# digit_7.net
KiCad netlist of a schematic drawn in EAGLE
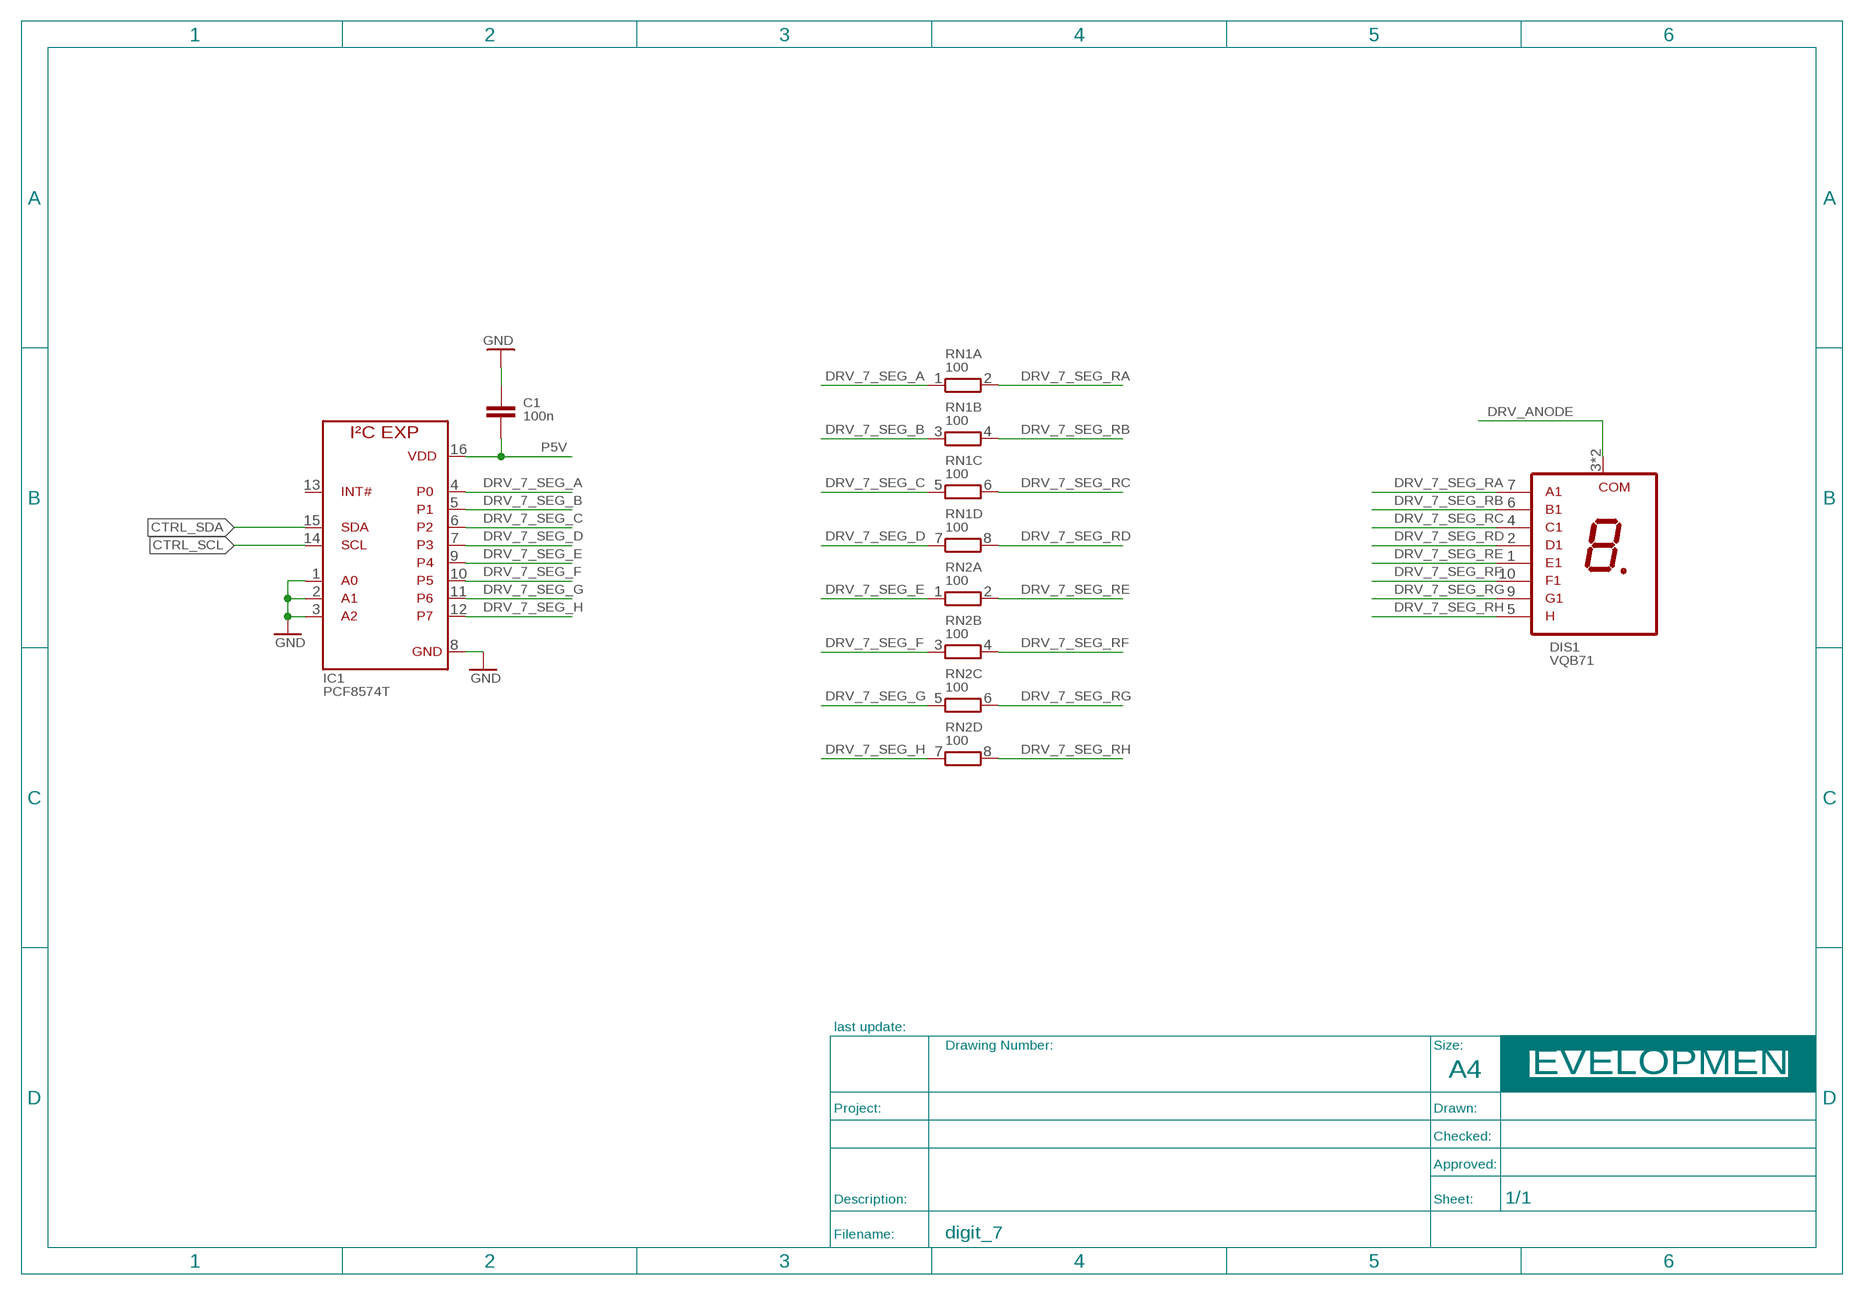
[diagram p0: schematic, sheet 1]

(export (version "E")
  (design (tool "Eeschema 10.0.6"))
  (components
    (comp (ref "C1")
      (value "100n")
      (footprint "eagle-import:S_0805")
      (fields (field (name "PART_CODE_BEL") "C_PAC_S_0805_VAL_100n"))
      (libsource (lib "eagle-import") (part "C_EU_S_0805"))
    )
    (comp (ref "DIS1")
      (value "VQB71")
      (footprint "eagle-import:T_VQB71")
      (libsource (lib "eagle-import") (part "VQB71"))
    )
    (comp (ref "IC1")
      (value "PCF8574T")
      (footprint "eagle-import:S_SOIC16")
      (libsource (lib "eagle-import") (part "PCF8574T"))
    )
    (comp (ref "RN1")
      (value "100")
      (footprint "eagle-import:T_SIL8")
      (fields (field (name "PART_CODE_BEL") "RN_PAC_T_SIL8_VAL_100"))
      (libsource (lib "eagle-import") (part "R_EU_ARRAY_4"))
    )
    (comp (ref "RN2")
      (value "100")
      (footprint "eagle-import:T_SIL8")
      (fields (field (name "PART_CODE_BEL") "RN_PAC_T_SIL8_VAL_100"))
      (libsource (lib "eagle-import") (part "R_EU_ARRAY_4"))
    )
  )
  (nets
    (net (code "1") (name "/DRV_7_SEG_A") (class "Default")
      (node (ref "IC1") (pin "4") (pinfunction "P0_4") (pintype "bidirectional"))
      (node (ref "RN1") (pin "1") (pinfunction "1_1") (pintype "passive"))
    )
    (net (code "2") (name "/DRV_7_SEG_B") (class "Default")
      (node (ref "IC1") (pin "5") (pinfunction "P1_5") (pintype "bidirectional"))
      (node (ref "RN1") (pin "3") (pinfunction "1_3") (pintype "passive"))
    )
    (net (code "3") (name "/DRV_7_SEG_C") (class "Default")
      (node (ref "IC1") (pin "6") (pinfunction "P2_6") (pintype "bidirectional"))
      (node (ref "RN1") (pin "5") (pinfunction "1_5") (pintype "passive"))
    )
    (net (code "4") (name "/DRV_7_SEG_D") (class "Default")
      (node (ref "IC1") (pin "7") (pinfunction "P3_7") (pintype "bidirectional"))
      (node (ref "RN1") (pin "7") (pinfunction "1_7") (pintype "passive"))
    )
    (net (code "5") (name "/DRV_7_SEG_E") (class "Default")
      (node (ref "IC1") (pin "9") (pinfunction "P4_9") (pintype "bidirectional"))
      (node (ref "RN2") (pin "1") (pinfunction "1_1") (pintype "passive"))
    )
    (net (code "6") (name "/DRV_7_SEG_F") (class "Default")
      (node (ref "IC1") (pin "10") (pinfunction "P5_10") (pintype "bidirectional"))
      (node (ref "RN2") (pin "3") (pinfunction "1_3") (pintype "passive"))
    )
    (net (code "7") (name "/DRV_7_SEG_G") (class "Default")
      (node (ref "IC1") (pin "11") (pinfunction "P6_11") (pintype "bidirectional"))
      (node (ref "RN2") (pin "5") (pinfunction "1_5") (pintype "passive"))
    )
    (net (code "8") (name "/DRV_7_SEG_H") (class "Default")
      (node (ref "IC1") (pin "12") (pinfunction "P7_12") (pintype "bidirectional"))
      (node (ref "RN2") (pin "7") (pinfunction "1_7") (pintype "passive"))
    )
    (net (code "9") (name "/DRV_7_SEG_RA") (class "Default")
      (node (ref "DIS1") (pin "7") (pinfunction "A1_7") (pintype "passive"))
      (node (ref "RN1") (pin "2") (pinfunction "2_2") (pintype "passive"))
    )
    (net (code "10") (name "/DRV_7_SEG_RB") (class "Default")
      (node (ref "DIS1") (pin "6") (pinfunction "B1_6") (pintype "passive"))
      (node (ref "RN1") (pin "4") (pinfunction "2_4") (pintype "passive"))
    )
    (net (code "11") (name "/DRV_7_SEG_RC") (class "Default")
      (node (ref "DIS1") (pin "4") (pinfunction "C1_4") (pintype "passive"))
      (node (ref "RN1") (pin "6") (pinfunction "2_6") (pintype "passive"))
    )
    (net (code "12") (name "/DRV_7_SEG_RD") (class "Default")
      (node (ref "DIS1") (pin "2") (pinfunction "D1_2") (pintype "passive"))
      (node (ref "RN1") (pin "8") (pinfunction "2_8") (pintype "passive"))
    )
    (net (code "13") (name "/DRV_7_SEG_RE") (class "Default")
      (node (ref "DIS1") (pin "1") (pinfunction "E1_1") (pintype "passive"))
      (node (ref "RN2") (pin "2") (pinfunction "2_2") (pintype "passive"))
    )
    (net (code "14") (name "/DRV_7_SEG_RF") (class "Default")
      (node (ref "DIS1") (pin "10") (pinfunction "F1_10") (pintype "passive"))
      (node (ref "RN2") (pin "4") (pinfunction "2_4") (pintype "passive"))
    )
    (net (code "15") (name "/DRV_7_SEG_RG") (class "Default")
      (node (ref "DIS1") (pin "9") (pinfunction "G1_9") (pintype "passive"))
      (node (ref "RN2") (pin "6") (pinfunction "2_6") (pintype "passive"))
    )
    (net (code "16") (name "/DRV_7_SEG_RH") (class "Default")
      (node (ref "DIS1") (pin "5") (pinfunction "DP1_5") (pintype "passive"))
      (node (ref "RN2") (pin "8") (pinfunction "2_8") (pintype "passive"))
    )
    (net (code "17") (name "/DRV_ANODE") (class "Default")
      (node (ref "DIS1") (pin "3") (pinfunction "COM1_3") (pintype "passive"))
      (node (ref "DIS1") (pin "8") (pinfunction "COM1_8") (pintype "passive"))
    )
    (net (code "18") (name "/P5V") (class "Default")
      (node (ref "C1") (pin "2") (pinfunction "2_2") (pintype "passive"))
      (node (ref "IC1") (pin "16") (pinfunction "VDD_16") (pintype "power_in"))
    )
    (net (code "19") (name "CTRL_SCL") (class "Default")
      (node (ref "IC1") (pin "14") (pinfunction "SCL_14") (pintype "input"))
    )
    (net (code "20") (name "CTRL_SDA") (class "Default")
      (node (ref "IC1") (pin "15") (pinfunction "SDA_15") (pintype "bidirectional"))
    )
    (net (code "21") (name "GND") (class "Default")
      (node (ref "C1") (pin "1") (pinfunction "1_1") (pintype "passive"))
      (node (ref "IC1") (pin "1") (pinfunction "A0_1") (pintype "input"))
      (node (ref "IC1") (pin "2") (pinfunction "A1_2") (pintype "input"))
      (node (ref "IC1") (pin "3") (pinfunction "A2_3") (pintype "input"))
      (node (ref "IC1") (pin "8") (pinfunction "GND_8") (pintype "power_in"))
    )
    (net (code "22") (name "unconnected-(IC1-~{INT}-Pad13)") (class "Default")
      (node (ref "IC1") (pin "13") (pinfunction "~{INT}_13") (pintype "output"))
    )
  )
)
